# Lipo_Rider_Plus.net
KiCad netlist of a schematic drawn in EAGLE
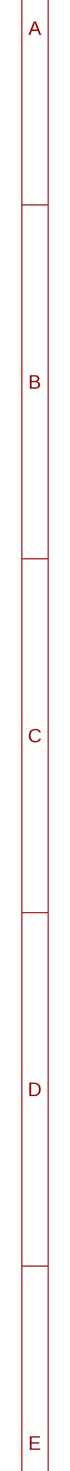
[diagram p0: schematic, sheet 1, part 1 of 2]
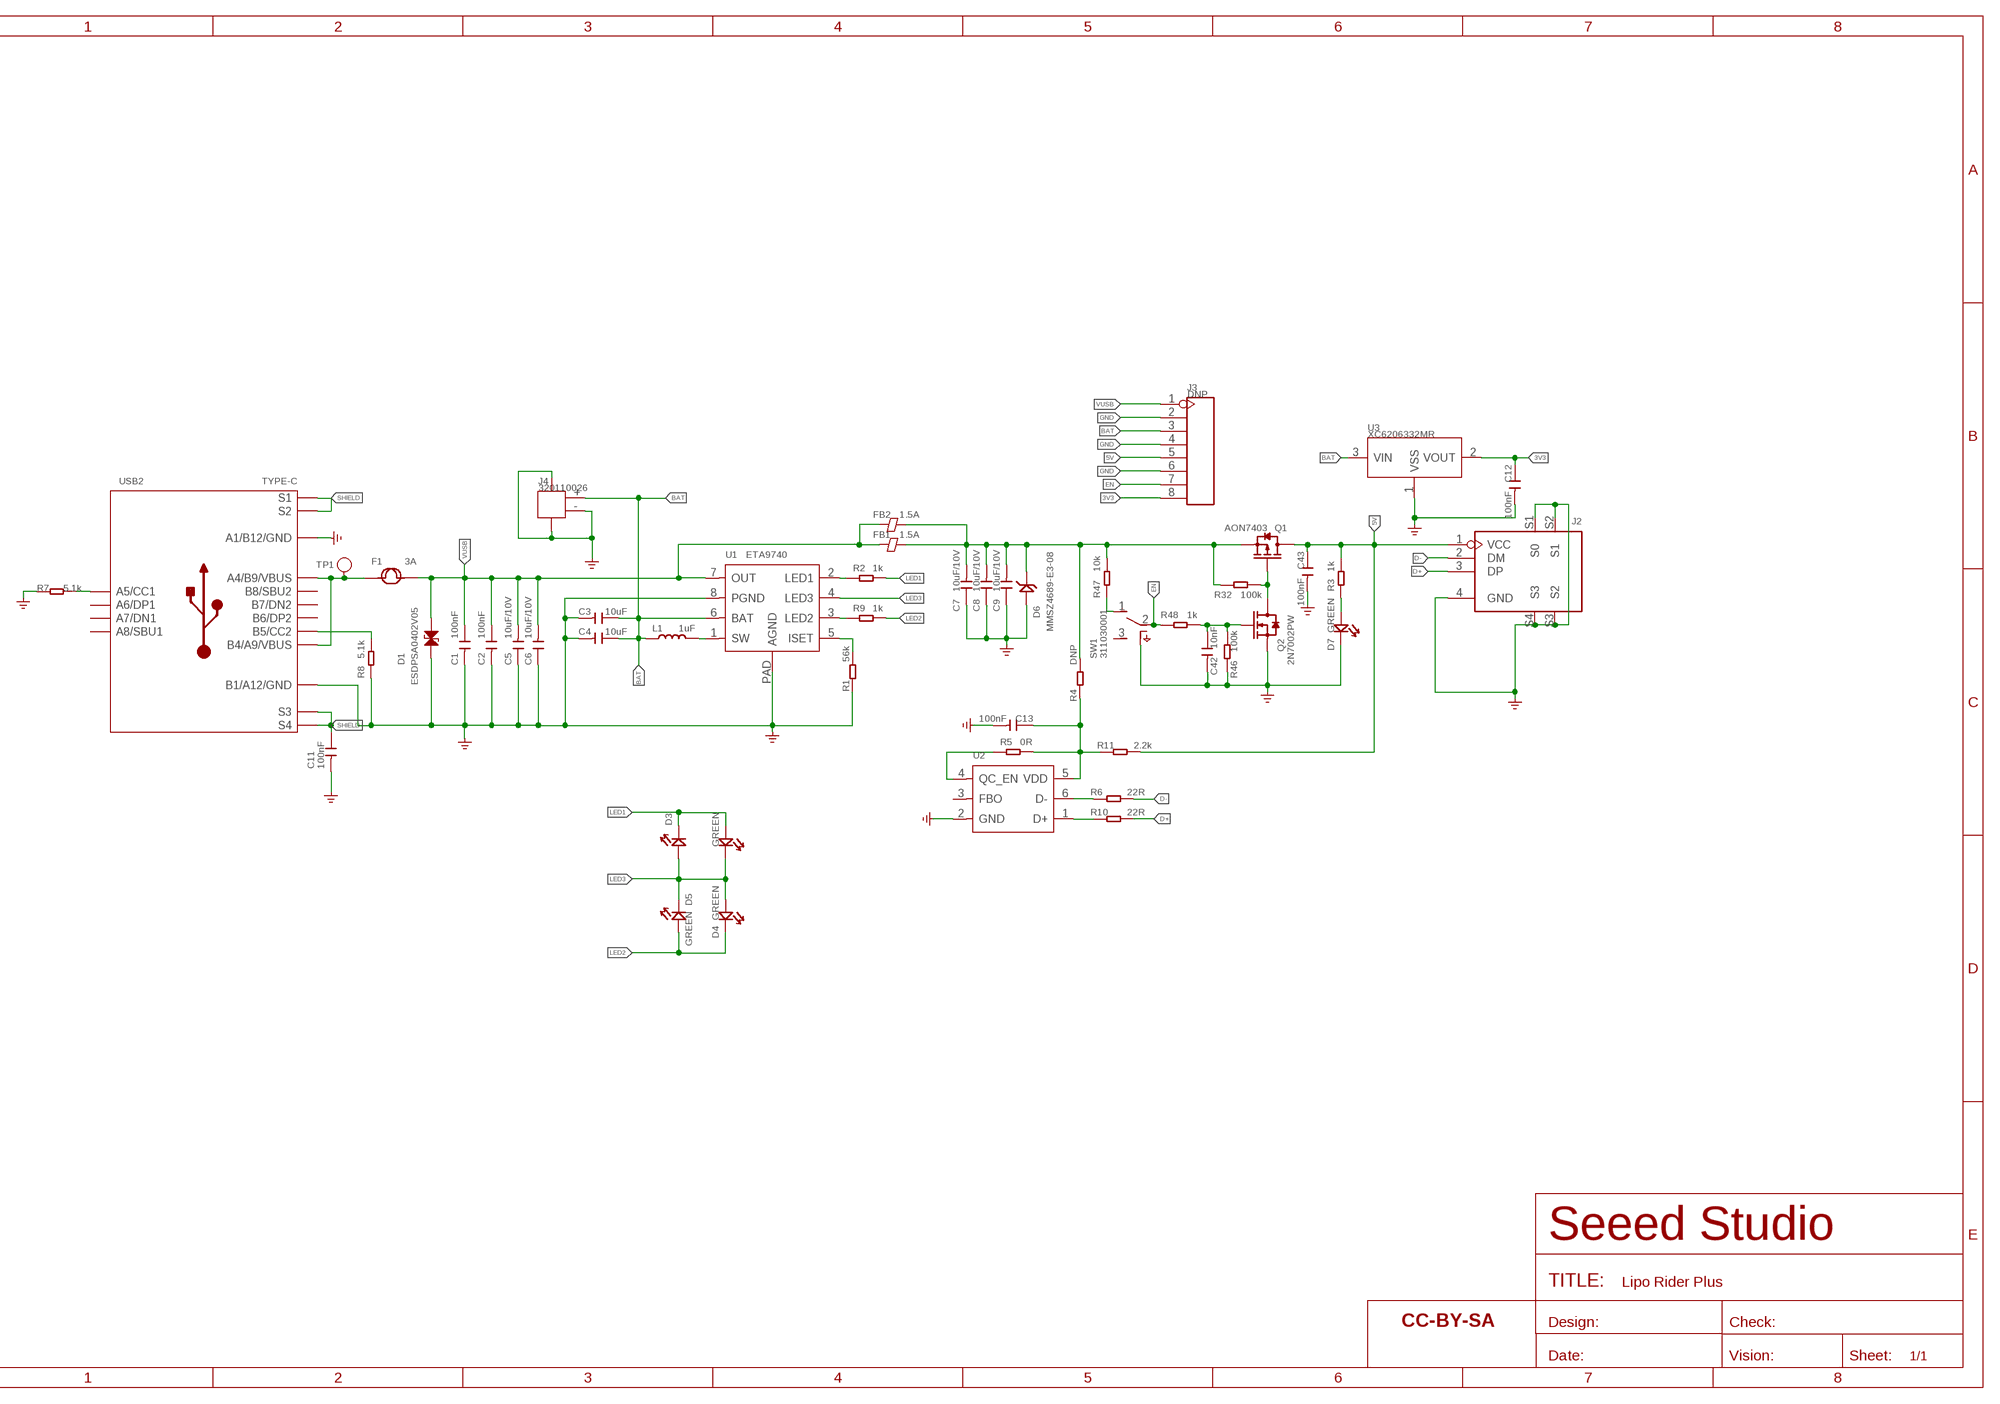
[diagram p1: schematic, sheet 1, part 2 of 2]

(export (version "E")
  (design (tool "Eeschema 10.0.6"))
  (components
    (comp (ref "C1")
      (value "100nF")
      (footprint "eagle-import:C0402")
      (libsource (lib "eagle-import") (part "CAP-0402"))
    )
    (comp (ref "C2")
      (value "100nF")
      (footprint "eagle-import:C0402")
      (libsource (lib "eagle-import") (part "CAP-0402"))
    )
    (comp (ref "C3")
      (value "10uF")
      (footprint "eagle-import:C0603")
      (libsource (lib "eagle-import") (part "CAP-0603"))
    )
    (comp (ref "C4")
      (value "10uF")
      (footprint "eagle-import:C0603")
      (libsource (lib "eagle-import") (part "CAP-0603"))
    )
    (comp (ref "C5")
      (value "10uF/10V")
      (footprint "eagle-import:C0805")
      (libsource (lib "eagle-import") (part "CAP-0805"))
    )
    (comp (ref "C6")
      (value "10uF/10V")
      (footprint "eagle-import:C0805")
      (libsource (lib "eagle-import") (part "CAP-0805"))
    )
    (comp (ref "C7")
      (value "10uF/10V")
      (footprint "eagle-import:C0805")
      (libsource (lib "eagle-import") (part "CAP-0805"))
    )
    (comp (ref "C8")
      (value "10uF/10V")
      (footprint "eagle-import:C0805")
      (libsource (lib "eagle-import") (part "CAP-0805"))
    )
    (comp (ref "C9")
      (value "10uF/10V")
      (footprint "eagle-import:C0805")
      (libsource (lib "eagle-import") (part "CAP-0805"))
    )
    (comp (ref "C11")
      (value "100nF")
      (footprint "eagle-import:C0402")
      (libsource (lib "eagle-import") (part "CAP-0402"))
    )
    (comp (ref "C12")
      (value "100nF")
      (footprint "eagle-import:C0402")
      (libsource (lib "eagle-import") (part "CAP-0402"))
    )
    (comp (ref "C13")
      (value "100nF")
      (footprint "eagle-import:C0402")
      (libsource (lib "eagle-import") (part "CAP-0402"))
    )
    (comp (ref "C42")
      (value "10nF")
      (footprint "eagle-import:C0402")
      (libsource (lib "eagle-import") (part "CAP-0402"))
    )
    (comp (ref "C43")
      (value "100nF")
      (footprint "eagle-import:C0402")
      (libsource (lib "eagle-import") (part "CAP-0402"))
    )
    (comp (ref "D1")
      (value "ESDPSA0402V05")
      (footprint "eagle-import:ESD-0402")
      (libsource (lib "eagle-import") (part "D-ESD-2P-DOUBLE-0402"))
    )
    (comp (ref "D2")
      (value "GREEN")
      (footprint "eagle-import:LED-0402")
      (libsource (lib "eagle-import") (part "LED-0402"))
    )
    (comp (ref "D3")
      (value "GREEN")
      (footprint "eagle-import:LED-0402")
      (libsource (lib "eagle-import") (part "LED-0402"))
    )
    (comp (ref "D4")
      (value "GREEN")
      (footprint "eagle-import:LED-0402")
      (libsource (lib "eagle-import") (part "LED-0402"))
    )
    (comp (ref "D5")
      (value "GREEN")
      (footprint "eagle-import:LED-0402")
      (libsource (lib "eagle-import") (part "LED-0402"))
    )
    (comp (ref "D6")
      (value "MMSZ4689-E3-08")
      (footprint "eagle-import:SOD-123")
      (libsource (lib "eagle-import") (part "D-ZENER-2P-304030008"))
    )
    (comp (ref "D7")
      (value "GREEN")
      (footprint "eagle-import:LED-0402")
      (libsource (lib "eagle-import") (part "LED-0402"))
    )
    (comp (ref "F1")
      (value "3A")
      (footprint "eagle-import:F1812")
      (libsource (lib "eagle-import") (part "FUSE'1812'"))
    )
    (comp (ref "FB1")
      (value "1.5A")
      (footprint "eagle-import:F0805")
      (libsource (lib "eagle-import") (part "FERRITE-BEAD-0805"))
    )
    (comp (ref "FB2")
      (value "1.5A")
      (footprint "eagle-import:F0805")
      (libsource (lib "eagle-import") (part "FERRITE-BEAD-0805"))
    )
    (comp (ref "FR1")
      (value "SEEEDSTUDIO-OPEN-SCH-FRAME-BIG")
      (footprint "eagle-import:SEEEDSTUDIO-PCB-FRAME")
      (libsource (lib "eagle-import") (part "SEEEDSTUDIO-OPEN-SCH-FRAME-BIG"))
    )
    (comp (ref "J2")
      (value "USB4+4P-SMD+DIP")
      (footprint "eagle-import:USB4+4P-2.0-14.6X10.6X5.72MM")
      (libsource (lib "eagle-import") (part "USB4+4P-SMD+DIP"))
    )
    (comp (ref "J3")
      (value "DNP")
      (footprint "eagle-import:H8-2.54-C65D35MIL")
      (libsource (lib "eagle-import") (part "HEADER-8P-65/35MIL"))
    )
    (comp (ref "J4")
      (value "320110026")
      (footprint "eagle-import:HW2-SMD-2.0-90D")
      (libsource (lib "eagle-import") (part "JST-2P-SMD'2.0'"))
    )
    (comp (ref "L1")
      (value "1uF")
      (footprint "eagle-import:L4.4X3.0MM")
      (libsource (lib "eagle-import") (part "INDUCTOR-4430"))
    )
    (comp (ref "Q1")
      (value "AON7403")
      (footprint "eagle-import:DFN8P-0.65-3X3X0.8MM")
      (libsource (lib "eagle-import") (part "MOSFET-P-AON7403"))
    )
    (comp (ref "Q2")
      (value "2N7002PW")
      (footprint "eagle-import:SOT-323")
      (libsource (lib "eagle-import") (part "MOSFET-N'SI1304BDL'"))
    )
    (comp (ref "R1")
      (value "56k")
      (footprint "eagle-import:R0402")
      (libsource (lib "eagle-import") (part "RES-0402"))
    )
    (comp (ref "R2")
      (value "1k")
      (footprint "eagle-import:R0402")
      (libsource (lib "eagle-import") (part "RES-0402"))
    )
    (comp (ref "R3")
      (value "1k")
      (footprint "eagle-import:R0402")
      (libsource (lib "eagle-import") (part "RES-0402"))
    )
    (comp (ref "R4")
      (value "DNP")
      (footprint "eagle-import:R0402")
      (libsource (lib "eagle-import") (part "RES-0402"))
    )
    (comp (ref "R5")
      (value "0R")
      (footprint "eagle-import:R0402")
      (libsource (lib "eagle-import") (part "RES-0402"))
    )
    (comp (ref "R6")
      (value "22R")
      (footprint "eagle-import:R0402")
      (libsource (lib "eagle-import") (part "RES-0402"))
    )
    (comp (ref "R7")
      (value "5.1k")
      (footprint "eagle-import:R0402")
      (libsource (lib "eagle-import") (part "RES-0402"))
    )
    (comp (ref "R8")
      (value "5.1k")
      (footprint "eagle-import:R0402")
      (libsource (lib "eagle-import") (part "RES-0402"))
    )
    (comp (ref "R9")
      (value "1k")
      (footprint "eagle-import:R0402")
      (libsource (lib "eagle-import") (part "RES-0402"))
    )
    (comp (ref "R10")
      (value "22R")
      (footprint "eagle-import:R0402")
      (libsource (lib "eagle-import") (part "RES-0402"))
    )
    (comp (ref "R11")
      (value "2.2k")
      (footprint "eagle-import:R0402")
      (libsource (lib "eagle-import") (part "RES-0402"))
    )
    (comp (ref "R32")
      (value "100k")
      (footprint "eagle-import:R0402")
      (libsource (lib "eagle-import") (part "RES-0402"))
    )
    (comp (ref "R46")
      (value "100k")
      (footprint "eagle-import:R0402")
      (libsource (lib "eagle-import") (part "RES-0402"))
    )
    (comp (ref "R47")
      (value "10k")
      (footprint "eagle-import:R0402")
      (libsource (lib "eagle-import") (part "RES-0402"))
    )
    (comp (ref "R48")
      (value "1k")
      (footprint "eagle-import:R0402")
      (libsource (lib "eagle-import") (part "RES-0402"))
    )
    (comp (ref "SW1")
      (value "311030001")
      (footprint "eagle-import:SW7-SMD-L6.7X2.7X3.2MM")
      (libsource (lib "eagle-import") (part "SWITCH-3+4P-311030001"))
    )
    (comp (ref "TP1")
      (value "TEST")
      (footprint "eagle-import:TP-D45MIL")
      (fields (field (name "PARTNO") "DNP"))
      (libsource (lib "eagle-import") (part "TEST-POINT'4545'"))
    )
    (comp (ref "U1")
      (value "ETA9740")
      (footprint "eagle-import:ESOP8L-1.27-5X3.9MM")
      (libsource (lib "eagle-import") (part "PMIC-ETA9740"))
    )
    (comp (ref "U2")
      (value "CONTROLLER-FP6601Q")
      (footprint "eagle-import:SOT-23-6")
      (libsource (lib "eagle-import") (part "CONTROLLER-FP6601Q"))
    )
    (comp (ref "U3")
      (value "XC6206332MR")
      (footprint "eagle-import:SOT-23")
      (libsource (lib "eagle-import") (part "PMIC-XC6206PMR"))
    )
    (comp (ref "USB2")
      (value "TYPE-C")
      (footprint "eagle-import:USB2.0-TYPE-C")
      (libsource (lib "eagle-import") (part "USB2.0-TYPE-C"))
    )
  )
  (nets
    (net (code "1") (name "3V3") (class "Default")
      (node (ref "C12") (pin "1") (pinfunction "1_1") (pintype "passive"))
      (node (ref "J3") (pin "8") (pinfunction "8_8") (pintype "bidirectional"))
      (node (ref "U3") (pin "2") (pinfunction "VOUT_2") (pintype "bidirectional"))
    )
    (net (code "2") (name "5V") (class "Default")
      (node (ref "C43") (pin "1") (pinfunction "1_1") (pintype "passive"))
      (node (ref "J2") (pin "1") (pinfunction "VCC_1") (pintype "bidirectional"))
      (node (ref "J3") (pin "5") (pinfunction "5_5") (pintype "bidirectional"))
      (node (ref "Q1") (pin "5") (pinfunction "D_5") (pintype "passive"))
      (node (ref "Q1") (pin "6") (pinfunction "D_6") (pintype "passive"))
      (node (ref "Q1") (pin "7") (pinfunction "D_7") (pintype "passive"))
      (node (ref "Q1") (pin "8") (pinfunction "D_8") (pintype "passive"))
      (node (ref "Q1") (pin "9") (pinfunction "D_9") (pintype "passive"))
      (node (ref "R11") (pin "2") (pinfunction "2_2") (pintype "passive"))
      (node (ref "R3") (pin "2") (pinfunction "2_2") (pintype "passive"))
    )
    (net (code "3") (name "BAT") (class "Default")
      (node (ref "C3") (pin "1") (pinfunction "1_1") (pintype "passive"))
      (node (ref "C4") (pin "1") (pinfunction "1_1") (pintype "passive"))
      (node (ref "J3") (pin "3") (pinfunction "3_3") (pintype "bidirectional"))
      (node (ref "J4") (pin "+") (pinfunction "1_+") (pintype "bidirectional"))
      (node (ref "L1") (pin "1") (pinfunction "1_1") (pintype "passive"))
      (node (ref "U1") (pin "6") (pinfunction "BAT_6") (pintype "bidirectional"))
      (node (ref "U3") (pin "3") (pinfunction "VIN_3") (pintype "bidirectional"))
    )
    (net (code "4") (name "D+") (class "Default")
      (node (ref "J2") (pin "3") (pinfunction "DP_3") (pintype "bidirectional"))
      (node (ref "R10") (pin "2") (pinfunction "2_2") (pintype "passive"))
    )
    (net (code "5") (name "D-") (class "Default")
      (node (ref "J2") (pin "2") (pinfunction "DM_2") (pintype "bidirectional"))
      (node (ref "R6") (pin "2") (pinfunction "2_2") (pintype "passive"))
    )
    (net (code "6") (name "EN") (class "Default")
      (node (ref "J3") (pin "7") (pinfunction "7_7") (pintype "bidirectional"))
      (node (ref "R48") (pin "1") (pinfunction "1_1") (pintype "passive"))
      (node (ref "SW1") (pin "2") (pinfunction "COM_2") (pintype "bidirectional"))
    )
    (net (code "7") (name "GND") (class "Default")
      (node (ref "C1") (pin "2") (pinfunction "2_2") (pintype "passive"))
      (node (ref "C11") (pin "2") (pinfunction "2_2") (pintype "passive"))
      (node (ref "C12") (pin "2") (pinfunction "2_2") (pintype "passive"))
      (node (ref "C13") (pin "2") (pinfunction "2_2") (pintype "passive"))
      (node (ref "C2") (pin "2") (pinfunction "2_2") (pintype "passive"))
      (node (ref "C3") (pin "2") (pinfunction "2_2") (pintype "passive"))
      (node (ref "C4") (pin "2") (pinfunction "2_2") (pintype "passive"))
      (node (ref "C42") (pin "2") (pinfunction "2_2") (pintype "passive"))
      (node (ref "C43") (pin "2") (pinfunction "2_2") (pintype "passive"))
      (node (ref "C5") (pin "1") (pinfunction "1_1") (pintype "passive"))
      (node (ref "C6") (pin "1") (pinfunction "1_1") (pintype "passive"))
      (node (ref "C7") (pin "1") (pinfunction "1_1") (pintype "passive"))
      (node (ref "C8") (pin "1") (pinfunction "1_1") (pintype "passive"))
      (node (ref "C9") (pin "1") (pinfunction "1_1") (pintype "passive"))
      (node (ref "D1") (pin "1") (pinfunction "1_1") (pintype "bidirectional"))
      (node (ref "D6") (pin "+") (pinfunction "+_+") (pintype "bidirectional"))
      (node (ref "D7") (pin "-") (pinfunction "-_-") (pintype "passive"))
      (node (ref "J2") (pin "4") (pinfunction "GND_4") (pintype "bidirectional"))
      (node (ref "J2") (pin "S1") (pinfunction "S0_S1") (pintype "bidirectional"))
      (node (ref "J2") (pin "S2") (pinfunction "S1_S2") (pintype "bidirectional"))
      (node (ref "J2") (pin "S3") (pinfunction "S2_S3") (pintype "bidirectional"))
      (node (ref "J2") (pin "S4") (pinfunction "S3_S4") (pintype "bidirectional"))
      (node (ref "J3") (pin "2") (pinfunction "2_2") (pintype "bidirectional"))
      (node (ref "J3") (pin "4") (pinfunction "4_4") (pintype "bidirectional"))
      (node (ref "J3") (pin "6") (pinfunction "6_6") (pintype "bidirectional"))
      (node (ref "J4") (pin "-") (pinfunction "2_-") (pintype "bidirectional"))
      (node (ref "J4") (pin "3") (pinfunction "3_3") (pintype "bidirectional"))
      (node (ref "J4") (pin "4") (pinfunction "4_4") (pintype "bidirectional"))
      (node (ref "Q2") (pin "2") (pinfunction "S_2") (pintype "passive"))
      (node (ref "R1") (pin "1") (pinfunction "1_1") (pintype "passive"))
      (node (ref "R46") (pin "1") (pinfunction "1_1") (pintype "passive"))
      (node (ref "R7") (pin "1") (pinfunction "1_1") (pintype "passive"))
      (node (ref "R8") (pin "2") (pinfunction "2_2") (pintype "passive"))
      (node (ref "SW1") (pin "SS1") (pinfunction "SS2_SS1") (pintype "bidirectional"))
      (node (ref "SW1") (pin "SS2") (pinfunction "SS2_SS2") (pintype "bidirectional"))
      (node (ref "SW1") (pin "SS3") (pinfunction "SS2_SS3") (pintype "bidirectional"))
      (node (ref "SW1") (pin "SS4") (pinfunction "SS2_SS4") (pintype "bidirectional"))
      (node (ref "U1") (pin "8") (pinfunction "PGND_8") (pintype "bidirectional"))
      (node (ref "U1") (pin "PAD") (pinfunction "AGND_PAD") (pintype "bidirectional"))
      (node (ref "U2") (pin "2") (pinfunction "GND_2") (pintype "bidirectional"))
      (node (ref "U3") (pin "1") (pinfunction "VSS_1") (pintype "bidirectional"))
      (node (ref "USB2") (pin "A1_B12") (pinfunction "A1/B12/GND_A1_B12") (pintype "bidirectional"))
      (node (ref "USB2") (pin "B1_A12") (pinfunction "B1/A12/GND_B1_A12") (pintype "bidirectional"))
    )
    (net (code "8") (name "LED1") (class "Default")
      (node (ref "D2") (pin "+") (pinfunction "+_+") (pintype "passive"))
      (node (ref "D3") (pin "-") (pinfunction "-_-") (pintype "passive"))
      (node (ref "R2") (pin "2") (pinfunction "2_2") (pintype "passive"))
    )
    (net (code "9") (name "LED2") (class "Default")
      (node (ref "D4") (pin "-") (pinfunction "-_-") (pintype "passive"))
      (node (ref "D5") (pin "+") (pinfunction "+_+") (pintype "passive"))
      (node (ref "R9") (pin "2") (pinfunction "2_2") (pintype "passive"))
    )
    (net (code "10") (name "LED3") (class "Default")
      (node (ref "D2") (pin "-") (pinfunction "-_-") (pintype "passive"))
      (node (ref "D3") (pin "+") (pinfunction "+_+") (pintype "passive"))
      (node (ref "D4") (pin "+") (pinfunction "+_+") (pintype "passive"))
      (node (ref "D5") (pin "-") (pinfunction "-_-") (pintype "passive"))
      (node (ref "U1") (pin "4") (pinfunction "LED3_4") (pintype "bidirectional"))
    )
    (net (code "11") (name "Net-(C7-Pad2)") (class "Default")
      (node (ref "C7") (pin "2") (pinfunction "2_2") (pintype "passive"))
      (node (ref "C8") (pin "2") (pinfunction "2_2") (pintype "passive"))
      (node (ref "C9") (pin "2") (pinfunction "2_2") (pintype "passive"))
      (node (ref "D6") (pin "-") (pinfunction "-_-") (pintype "bidirectional"))
      (node (ref "FB1") (pin "2") (pinfunction "2_2") (pintype "bidirectional"))
      (node (ref "FB2") (pin "2") (pinfunction "2_2") (pintype "bidirectional"))
      (node (ref "Q1") (pin "1") (pinfunction "S_1") (pintype "passive"))
      (node (ref "Q1") (pin "2") (pinfunction "S_2") (pintype "passive"))
      (node (ref "Q1") (pin "3") (pinfunction "S_3") (pintype "passive"))
      (node (ref "R32") (pin "1") (pinfunction "1_1") (pintype "passive"))
      (node (ref "R4") (pin "2") (pinfunction "2_2") (pintype "passive"))
      (node (ref "R47") (pin "2") (pinfunction "2_2") (pintype "passive"))
    )
    (net (code "12") (name "Net-(D7-Pad+)") (class "Default")
      (node (ref "D7") (pin "+") (pinfunction "+_+") (pintype "passive"))
      (node (ref "R3") (pin "1") (pinfunction "1_1") (pintype "passive"))
    )
    (net (code "13") (name "Net-(Q1-G)") (class "Default")
      (node (ref "Q1") (pin "4") (pinfunction "G_4") (pintype "passive"))
      (node (ref "Q2") (pin "3") (pinfunction "D_3") (pintype "passive"))
      (node (ref "R32") (pin "2") (pinfunction "2_2") (pintype "passive"))
    )
    (net (code "14") (name "Net-(Q2-G)") (class "Default")
      (node (ref "C42") (pin "1") (pinfunction "1_1") (pintype "passive"))
      (node (ref "Q2") (pin "1") (pinfunction "G_1") (pintype "passive"))
      (node (ref "R46") (pin "2") (pinfunction "2_2") (pintype "passive"))
      (node (ref "R48") (pin "2") (pinfunction "2_2") (pintype "passive"))
    )
    (net (code "15") (name "Net-(SW1-A)") (class "Default")
      (node (ref "R47") (pin "1") (pinfunction "1_1") (pintype "passive"))
      (node (ref "SW1") (pin "1") (pinfunction "A_1") (pintype "bidirectional"))
    )
    (net (code "16") (name "Net-(U1-ISET)") (class "Default")
      (node (ref "R1") (pin "2") (pinfunction "2_2") (pintype "passive"))
      (node (ref "U1") (pin "5") (pinfunction "ISET_5") (pintype "bidirectional"))
    )
    (net (code "17") (name "Net-(U1-LED1)") (class "Default")
      (node (ref "R2") (pin "1") (pinfunction "1_1") (pintype "passive"))
      (node (ref "U1") (pin "2") (pinfunction "LED1_2") (pintype "bidirectional"))
    )
    (net (code "18") (name "Net-(U1-LED2)") (class "Default")
      (node (ref "R9") (pin "1") (pinfunction "1_1") (pintype "passive"))
      (node (ref "U1") (pin "3") (pinfunction "LED2_3") (pintype "bidirectional"))
    )
    (net (code "19") (name "Net-(U1-SW)") (class "Default")
      (node (ref "L1") (pin "2") (pinfunction "2_2") (pintype "passive"))
      (node (ref "U1") (pin "1") (pinfunction "SW_1") (pintype "bidirectional"))
    )
    (net (code "20") (name "Net-(U2-D+)") (class "Default")
      (node (ref "R10") (pin "1") (pinfunction "1_1") (pintype "passive"))
      (node (ref "U2") (pin "1") (pinfunction "D+_1") (pintype "bidirectional"))
    )
    (net (code "21") (name "Net-(U2-D-)") (class "Default")
      (node (ref "R6") (pin "1") (pinfunction "1_1") (pintype "passive"))
      (node (ref "U2") (pin "6") (pinfunction "D-_6") (pintype "bidirectional"))
    )
    (net (code "22") (name "Net-(U2-QC_EN)") (class "Default")
      (node (ref "R5") (pin "1") (pinfunction "1_1") (pintype "passive"))
      (node (ref "U2") (pin "4") (pinfunction "QC_EN_4") (pintype "bidirectional"))
    )
    (net (code "23") (name "Net-(U2-VDD)") (class "Default")
      (node (ref "C13") (pin "1") (pinfunction "1_1") (pintype "passive"))
      (node (ref "R11") (pin "1") (pinfunction "1_1") (pintype "passive"))
      (node (ref "R4") (pin "1") (pinfunction "1_1") (pintype "passive"))
      (node (ref "R5") (pin "2") (pinfunction "2_2") (pintype "passive"))
      (node (ref "U2") (pin "5") (pinfunction "VDD_5") (pintype "bidirectional"))
    )
    (net (code "24") (name "Net-(USB2-A4{slash}B9{slash}VBUS)") (class "Default")
      (node (ref "F1") (pin "1") (pinfunction "1_1") (pintype "bidirectional"))
      (node (ref "TP1") (pin "T") (pinfunction "T_T") (pintype "bidirectional"))
      (node (ref "USB2") (pin "A4_B9") (pinfunction "A4/B9/VBUS_A4_B9") (pintype "bidirectional"))
      (node (ref "USB2") (pin "B4_A9") (pinfunction "B4/A9/VBUS_B4_A9") (pintype "bidirectional"))
    )
    (net (code "25") (name "Net-(USB2-A5{slash}CC1)") (class "Default")
      (node (ref "R7") (pin "2") (pinfunction "2_2") (pintype "passive"))
      (node (ref "USB2") (pin "A5") (pinfunction "A5/CC1_A5") (pintype "bidirectional"))
    )
    (net (code "26") (name "Net-(USB2-B5{slash}CC2)") (class "Default")
      (node (ref "R8") (pin "1") (pinfunction "1_1") (pintype "passive"))
      (node (ref "USB2") (pin "B5") (pinfunction "B5/CC2_B5") (pintype "bidirectional"))
    )
    (net (code "27") (name "SHIELD") (class "Default")
      (node (ref "C11") (pin "1") (pinfunction "1_1") (pintype "passive"))
      (node (ref "USB2") (pin "S1") (pinfunction "S1_S1") (pintype "bidirectional"))
      (node (ref "USB2") (pin "S2") (pinfunction "S2_S2") (pintype "bidirectional"))
      (node (ref "USB2") (pin "S3") (pinfunction "S3_S3") (pintype "bidirectional"))
      (node (ref "USB2") (pin "S4") (pinfunction "S4_S4") (pintype "bidirectional"))
      (node (ref "USB2") (pin "S5") (pinfunction "S1_S5") (pintype "bidirectional"))
      (node (ref "USB2") (pin "S6") (pinfunction "S2_S6") (pintype "bidirectional"))
    )
    (net (code "28") (name "VUSB") (class "Default")
      (node (ref "C1") (pin "1") (pinfunction "1_1") (pintype "passive"))
      (node (ref "C2") (pin "1") (pinfunction "1_1") (pintype "passive"))
      (node (ref "C5") (pin "2") (pinfunction "2_2") (pintype "passive"))
      (node (ref "C6") (pin "2") (pinfunction "2_2") (pintype "passive"))
      (node (ref "D1") (pin "2") (pinfunction "2_2") (pintype "bidirectional"))
      (node (ref "F1") (pin "2") (pinfunction "2_2") (pintype "bidirectional"))
      (node (ref "FB1") (pin "1") (pinfunction "1_1") (pintype "bidirectional"))
      (node (ref "FB2") (pin "1") (pinfunction "1_1") (pintype "bidirectional"))
      (node (ref "J3") (pin "1") (pinfunction "1_1") (pintype "bidirectional"))
      (node (ref "U1") (pin "7") (pinfunction "OUT_7") (pintype "bidirectional"))
    )
    (net (code "29") (name "unconnected-(SW1-B-Pad3)") (class "Default")
      (node (ref "SW1") (pin "3") (pinfunction "B_3") (pintype "bidirectional"))
    )
    (net (code "30") (name "unconnected-(U2-FBO-Pad3)") (class "Default")
      (node (ref "U2") (pin "3") (pinfunction "FBO_3") (pintype "bidirectional"))
    )
    (net (code "31") (name "unconnected-(USB2-A6{slash}DP1-PadA6)") (class "Default")
      (node (ref "USB2") (pin "A6") (pinfunction "A6/DP1_A6") (pintype "bidirectional"))
    )
    (net (code "32") (name "unconnected-(USB2-A7{slash}DN1-PadA7)") (class "Default")
      (node (ref "USB2") (pin "A7") (pinfunction "A7/DN1_A7") (pintype "bidirectional"))
    )
    (net (code "33") (name "unconnected-(USB2-A8{slash}SBU1-PadA8)") (class "Default")
      (node (ref "USB2") (pin "A8") (pinfunction "A8/SBU1_A8") (pintype "bidirectional"))
    )
    (net (code "34") (name "unconnected-(USB2-B6{slash}DP2-PadB6)") (class "Default")
      (node (ref "USB2") (pin "B6") (pinfunction "B6/DP2_B6") (pintype "bidirectional"))
    )
    (net (code "35") (name "unconnected-(USB2-B7{slash}DN2-PadB7)") (class "Default")
      (node (ref "USB2") (pin "B7") (pinfunction "B7/DN2_B7") (pintype "bidirectional"))
    )
    (net (code "36") (name "unconnected-(USB2-B8{slash}SBU2-PadB8)") (class "Default")
      (node (ref "USB2") (pin "B8") (pinfunction "B8/SBU2_B8") (pintype "bidirectional"))
    )
  )
)
